# PA_Channel.net
KiCad netlist of a schematic drawn in Altium Designer
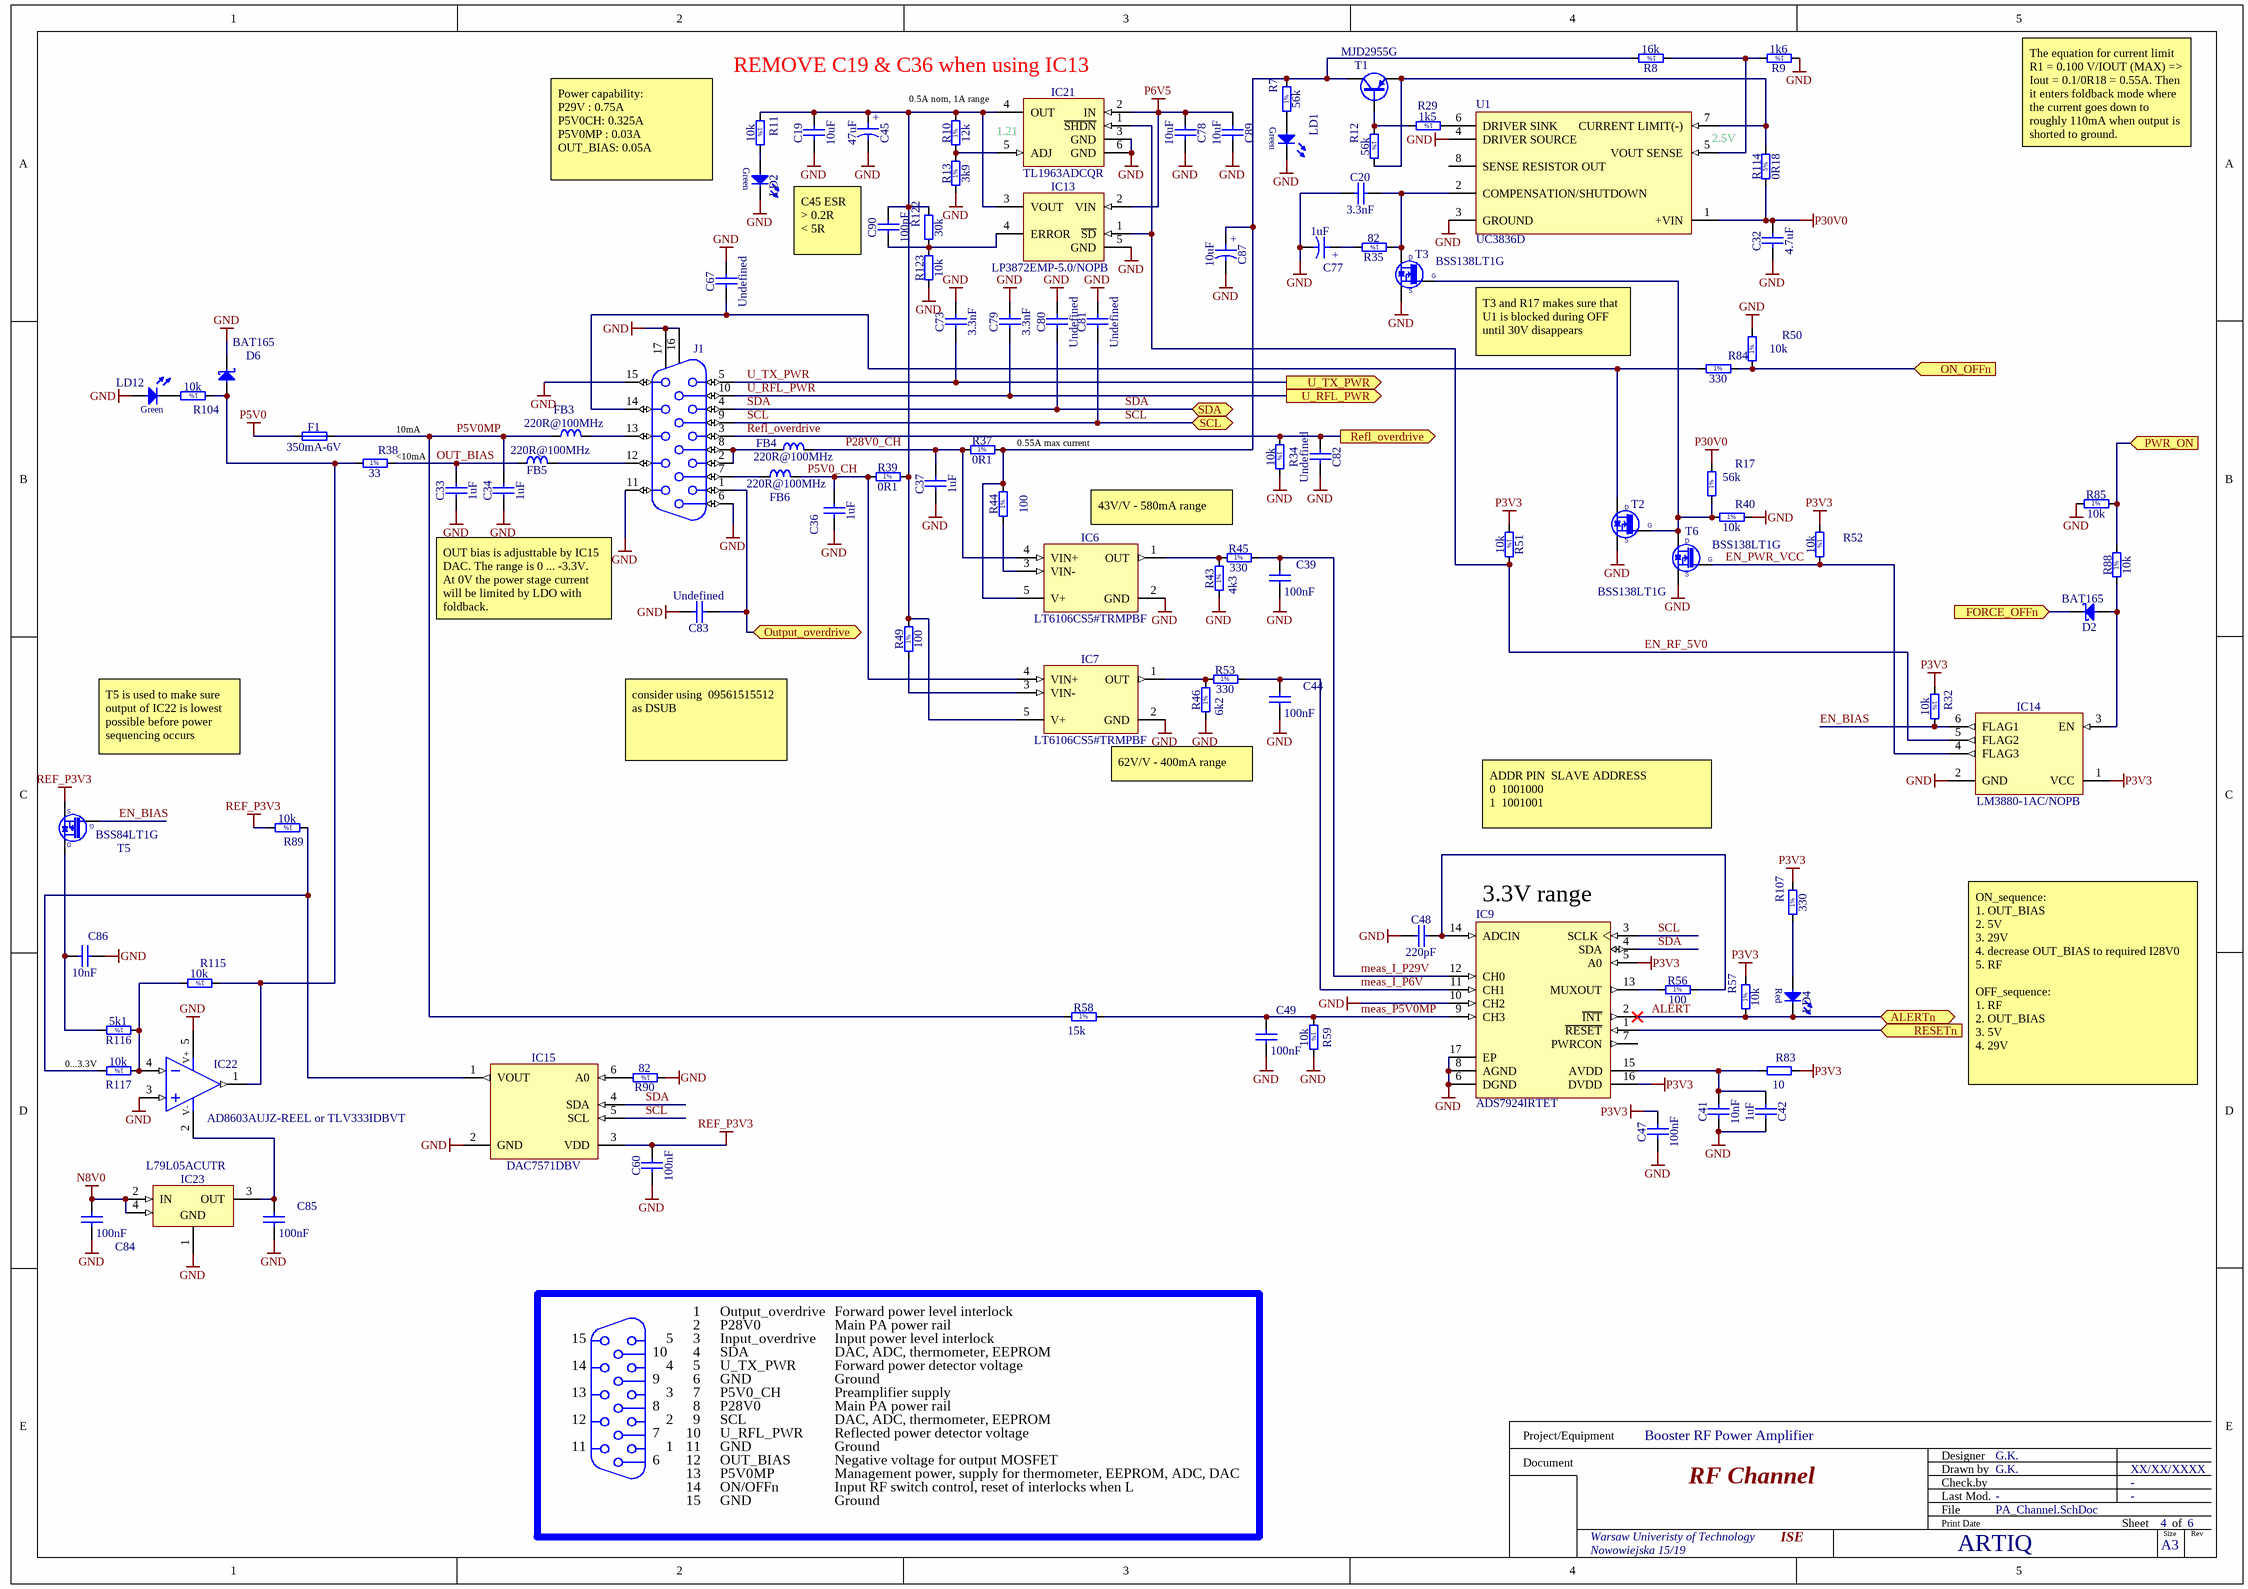
[diagram p0: PA_Channel.SchDoc]

(export (version "E")
  (design (tool "Eeschema 10.0.6"))
  (components
    (comp (ref "C19")
      (value "10uF")
      (footprint "CAPC2012X135N")
      (description "Non-polarised capacitor")
      (fields (field (name "PART NUMBER") "CC0805_10UF_16V_10%_X5R") (field (name "VOLTAGE") "16V"))
      (libsource (lib "Capacitors") (part "Capacitor - non polarized"))
    )
    (comp (ref "C20")
      (value "3.3nF")
      (footprint "CAPC1005X55N")
      (description "Non-polarised capacitor")
      (fields (field (name "PART NUMBER") "CC0402_3.3NF_50V_10%_X7R") (field (name "VOLTAGE") "50V"))
      (libsource (lib "Capacitors") (part "Capacitor - non polarized"))
    )
    (comp (ref "C32")
      (value "4.7uF")
      (footprint "CAPC3216X180N")
      (description "Non-polarised capacitor")
      (fields (field (name "PART NUMBER") "CC1206_4.7UF_50V_+80%-20%_Y5V") (field (name "VOLTAGE") "50V"))
      (libsource (lib "Capacitors") (part "Capacitor - non polarized"))
    )
    (comp (ref "C33")
      (value "1uF")
      (footprint "CAPC2012X110N")
      (description "Non-polarised capacitor")
      (fields (field (name "PART NUMBER") "CC0805_1UF_50V_10%_X7R") (field (name "VOLTAGE") "50V"))
      (libsource (lib "Capacitors") (part "Capacitor - non polarized"))
    )
    (comp (ref "C34")
      (value "1uF")
      (footprint "CAPC2012X110N")
      (description "Non-polarised capacitor")
      (fields (field (name "PART NUMBER") "CC0805_1UF_50V_10%_X7R") (field (name "VOLTAGE") "50V"))
      (libsource (lib "Capacitors") (part "Capacitor - non polarized"))
    )
    (comp (ref "C36")
      (value "1uF")
      (footprint "CAPC2012X110N")
      (description "Non-polarised capacitor")
      (fields (field (name "PART NUMBER") "CC0805_1UF_50V_10%_X7R") (field (name "VOLTAGE") "50V"))
      (libsource (lib "Capacitors") (part "Capacitor - non polarized"))
    )
    (comp (ref "C37")
      (value "1uF")
      (footprint "CAPC2012X110N")
      (description "Non-polarised capacitor")
      (fields (field (name "PART NUMBER") "CC0805_1UF_50V_10%_X7R") (field (name "VOLTAGE") "50V"))
      (libsource (lib "Capacitors") (part "Capacitor - non polarized"))
    )
    (comp (ref "C39")
      (value "100nF")
      (footprint "CAPC1005X55N")
      (description "Non-polarised capacitor")
      (fields (field (name "PART NUMBER") "CC0402_100NF_16V_10%_X7R") (field (name "VOLTAGE") "16V"))
      (libsource (lib "Capacitors") (part "Capacitor - non polarized"))
    )
    (comp (ref "C41")
      (value "10nF")
      (footprint "CAPC1005X55N")
      (description "Non-polarised capacitor")
      (fields (field (name "PART NUMBER") "CC0402_10NF_16V_10%_X7R") (field (name "VOLTAGE") "16V"))
      (libsource (lib "Capacitors") (part "Capacitor - non polarized"))
    )
    (comp (ref "C42")
      (value "1uF")
      (footprint "CAPC1005X55N")
      (description "Non-polarised capacitor")
      (fields (field (name "PART NUMBER") "CC0402_1UF_16V_10%_X5R") (field (name "VOLTAGE") "16V"))
      (libsource (lib "Capacitors") (part "Capacitor - non polarized"))
    )
    (comp (ref "C44")
      (value "100nF")
      (footprint "CAPC1005X55N")
      (description "Non-polarised capacitor")
      (fields (field (name "PART NUMBER") "CC0402_100NF_16V_10%_X7R") (field (name "VOLTAGE") "16V"))
      (libsource (lib "Capacitors") (part "Capacitor - non polarized"))
    )
    (comp (ref "C45")
      (value "47uF")
      (footprint "CAPMP3528X210N")
      (description "Polarised capacitor")
      (fields
        (field (name "PART NUMBER") "CTE3528-21_47UF_6.3V_10%_LESR0250")
        (field (name "VOLTAGE") "6.3V")
      )
      (libsource (lib "Capacitors") (part "Capacitor - polarized"))
    )
    (comp (ref "C47")
      (value "100nF")
      (footprint "CAPC1005X55N")
      (description "Non-polarised capacitor")
      (fields (field (name "PART NUMBER") "CC0402_100NF_16V_10%_X7R") (field (name "VOLTAGE") "16V"))
      (libsource (lib "Capacitors") (part "Capacitor - non polarized"))
    )
    (comp (ref "C48")
      (value "220pF")
      (footprint "CAPC1005X55N")
      (description "Non-polarised capacitor")
      (fields (field (name "PART NUMBER") "CC0402_220PF_50V_5%_C0G") (field (name "MANUFACTURER") "GENERIC"))
      (libsource (lib "Capacitors") (part "Capacitor - non polarized"))
    )
    (comp (ref "C49")
      (value "100nF")
      (footprint "CAPC1005X55N")
      (description "Non-polarised capacitor")
      (fields (field (name "PART NUMBER") "CC0402_100NF_16V_10%_X7R") (field (name "VOLTAGE") "16V"))
      (libsource (lib "Capacitors") (part "Capacitor - non polarized"))
    )
    (comp (ref "C60")
      (value "100nF")
      (footprint "CAPC1005X55N")
      (description "Non-polarised capacitor")
      (fields (field (name "PART NUMBER") "CC0402_100NF_16V_10%_X7R") (field (name "VOLTAGE") "16V"))
      (libsource (lib "Capacitors") (part "Capacitor - non polarized"))
    )
    (comp (ref "C67")
      (value "Undefined")
      (footprint "CAPC1005X55N")
      (description "Non-polarised capacitor")
      (fields (field (name "PART NUMBER") "CC0402_NO-VALUE"))
      (libsource (lib "Capacitors") (part "Capacitor - non polarized"))
    )
    (comp (ref "C73")
      (value "3.3nF")
      (footprint "CAPC1005X55N")
      (description "Non-polarised capacitor")
      (fields (field (name "PART NUMBER") "CC0402_3.3NF_50V_10%_X7R") (field (name "MANUFACTURER") "GENERIC"))
      (libsource (lib "Capacitors") (part "Capacitor - non polarized"))
    )
    (comp (ref "C77")
      (value "1uF")
      (footprint "CAPMP3216X180N")
      (description "Polarised capacitor")
      (fields (field (name "PART NUMBER") "CTE3216-18_1UF_16V_10%") (field (name "VOLTAGE") "16V"))
      (libsource (lib "Capacitors") (part "Capacitor - polarized"))
    )
    (comp (ref "C78")
      (value "10uF")
      (footprint "CAPC2012X135N")
      (description "Non-polarised capacitor")
      (fields (field (name "PART NUMBER") "CC0805_10UF_16V_10%_X5R") (field (name "VOLTAGE") "16V"))
      (libsource (lib "Capacitors") (part "Capacitor - non polarized"))
    )
    (comp (ref "C79")
      (value "3.3nF")
      (footprint "CAPC1005X55N")
      (description "Non-polarised capacitor")
      (fields (field (name "PART NUMBER") "CC0402_3.3NF_50V_10%_X7R") (field (name "MANUFACTURER") "GENERIC"))
      (libsource (lib "Capacitors") (part "Capacitor - non polarized"))
    )
    (comp (ref "C80")
      (value "Undefined")
      (footprint "CAPC1005X55N")
      (description "Non-polarised capacitor")
      (fields (field (name "PART NUMBER") "CC0402_NO-VALUE"))
      (libsource (lib "Capacitors") (part "Capacitor - non polarized"))
    )
    (comp (ref "C81")
      (value "Undefined")
      (footprint "CAPC1005X55N")
      (description "Non-polarised capacitor")
      (fields (field (name "PART NUMBER") "CC0402_NO-VALUE"))
      (libsource (lib "Capacitors") (part "Capacitor - non polarized"))
    )
    (comp (ref "C82")
      (value "Undefined")
      (footprint "CAPC1005X55N")
      (description "Non-polarised capacitor")
      (fields (field (name "PART NUMBER") "CC0402_NO-VALUE"))
      (libsource (lib "Capacitors") (part "Capacitor - non polarized"))
    )
    (comp (ref "C83")
      (value "Undefined")
      (footprint "CAPC1005X55N")
      (description "Non-polarised capacitor")
      (fields (field (name "PART NUMBER") "CC0402_NO-VALUE"))
      (libsource (lib "Capacitors") (part "Capacitor - non polarized"))
    )
    (comp (ref "C84")
      (value "100nF")
      (footprint "CAPC1005X55N")
      (description "Non-polarised capacitor")
      (fields (field (name "PART NUMBER") "CC0402_100NF_16V_10%_X7R") (field (name "VOLTAGE") "16V"))
      (libsource (lib "Capacitors") (part "Capacitor - non polarized"))
    )
    (comp (ref "C85")
      (value "100nF")
      (footprint "CAPC1005X55N")
      (description "Non-polarised capacitor")
      (fields (field (name "PART NUMBER") "CC0402_100NF_16V_10%_X7R") (field (name "VOLTAGE") "16V"))
      (libsource (lib "Capacitors") (part "Capacitor - non polarized"))
    )
    (comp (ref "C86")
      (value "10nF")
      (footprint "CAPC1608X87N")
      (description "Non-polarised capacitor")
      (fields (field (name "PART NUMBER") "CC0603_10NF_50V_5%_C0G") (field (name "VOLTAGE") "50V"))
      (libsource (lib "Capacitors") (part "Capacitor - non polarized"))
    )
    (comp (ref "C87")
      (value "10uF")
      (footprint "CAPMP6032X280N")
      (description "Polarised capacitor")
      (fields (field (name "PART NUMBER") "CTE6032-28_10UF_35V_10%") (field (name "VOLTAGE") "35V"))
      (libsource (lib "Capacitors") (part "Capacitor - polarized"))
    )
    (comp (ref "C89")
      (value "10uF")
      (footprint "CAPC2012X135N")
      (description "Non-polarised capacitor")
      (fields (field (name "PART NUMBER") "CC0805_10UF_16V_10%_X5R") (field (name "VOLTAGE") "16V"))
      (libsource (lib "Capacitors") (part "Capacitor - non polarized"))
    )
    (comp (ref "C90")
      (value "100pF")
      (footprint "CAPC1005X55N")
      (description "Non-polarised capacitor")
      (fields (field (name "PART NUMBER") "CC0402_100PF_50V_5%_C0G") (field (name "VOLTAGE") "50V"))
      (libsource (lib "Capacitors") (part "Capacitor - non polarized"))
    )
    (comp (ref "D2")
      (value "BAT165")
      (footprint "SOD2512X110N")
      (description "Schottky Diode")
      (fields (field (name "VOLTAGE") "40V") (field (name "POWER") "750mA"))
      (libsource (lib "ICs And Semiconductors") (part "Diode Schottky"))
    )
    (comp (ref "D6")
      (value "BAT165")
      (footprint "SOD2512X110N")
      (description "Schottky Diode")
      (fields (field (name "VOLTAGE") "40V") (field (name "POWER") "750mA"))
      (libsource (lib "ICs And Semiconductors") (part "Diode Schottky"))
    )
    (comp (ref "F1")
      (value "350mA-6V")
      (footprint "FUSR_TYCO_MICROSMD035F")
      (description "Fuse")
      (fields
        (field (name "PART NUMBER") "FUSR1210_TYCO_MICROSMD035F-2")
        (field (name "MANUFACTURER") "TYCO ELECTRONICS")
      )
      (libsource (lib "Eletro-mechanical") (part "Fuse"))
    )
    (comp (ref "FB3")
      (value "220R@100MHz")
      (footprint "INDC2012X105N")
      (description "Inductor")
      (fields (field (name "PART NUMBER") "IND0805_MURATA_BLM21PG221SN1D") (field (name "POWER") "2A"))
      (libsource (lib "Inductors & Transformers") (part "Inductor"))
    )
    (comp (ref "FB4")
      (value "220R@100MHz")
      (footprint "INDC2012X105N")
      (description "Inductor")
      (fields (field (name "PART NUMBER") "IND0805_MURATA_BLM21PG221SN1D") (field (name "POWER") "2A"))
      (libsource (lib "Inductors & Transformers") (part "Inductor"))
    )
    (comp (ref "FB5")
      (value "220R@100MHz")
      (footprint "INDC2012X105N")
      (description "Inductor")
      (fields (field (name "PART NUMBER") "IND0805_MURATA_BLM21PG221SN1D") (field (name "POWER") "2A"))
      (libsource (lib "Inductors & Transformers") (part "Inductor"))
    )
    (comp (ref "FB6")
      (value "220R@100MHz")
      (footprint "INDC2012X105N")
      (description "Inductor")
      (fields (field (name "PART NUMBER") "IND0805_MURATA_BLM21PG221SN1D") (field (name "POWER") "2A"))
      (libsource (lib "Inductors & Transformers") (part "Inductor"))
    )
    (comp (ref "IC6")
      (value "LT6106CS5#TRMPBF")
      (footprint "SOT95P280X145-5N")
      (description "Current Shunt Monitor -16V to +80V Common-Mode Range")
      (fields (field (name "MANUFACTURER") "ANALOG DEVICES"))
      (libsource (lib "ICs_Analog_Interfaces") (part "AMP_LT6106"))
    )
    (comp (ref "IC7")
      (value "LT6106CS5#TRMPBF")
      (footprint "SOT95P280X145-5N")
      (description "Current Shunt Monitor -16V to +80V Common-Mode Range")
      (fields (field (name "MANUFACTURER") "ANALOG DEVICES"))
      (libsource (lib "ICs_Analog_Interfaces") (part "AMP_LT6106"))
    )
    (comp (ref "IC9")
      (value "ADS7924IRTET")
      (footprint "TI-RTE16-1700X1700TP_V")
      (fields (field (name "MANUFACTURER") "Texas Instruments"))
      (libsource (lib "Altium Content Vault") (part "CMP-0003-02162-1"))
    )
    (comp (ref "IC13")
      (value "LP3872EMP-5.0/NOPB")
      (footprint "SOT150P700X180-5N")
      (description "1.5-A, low-dropout voltage regulator with  enable")
      (fields (field (name "MANUFACTURER") "TEXAS INSTRUMENTS"))
      (libsource (lib "Regulators_SMPS") (part "REG_LP3872EMP-5.0/NOPB"))
    )
    (comp (ref "IC14")
      (value "LM3880-1AC/NOPB")
      (footprint "SOT95P280X145-6N")
      (description "Simple Power Sequencer")
      (fields (field (name "MANUFACTURER") "TEXAS INSTRUMENTS"))
      (libsource (lib "ICs And Semiconductors") (part "LM3880"))
    )
    (comp (ref "IC15")
      (value "DAC7571DBV")
      (footprint "SOT95P280X145-6N")
      (description "+2.7 V to +5.5 V, I2C Interface (Receive Only), Voltage Output, 12-Bit Digital-To-Analog Converter")
      (fields (field (name "MANUFACTURER") "TEXAS INSTRUMENTS"))
      (libsource (lib "ICs And Semiconductors") (part "DAC7571"))
    )
    (comp (ref "IC21")
      (value "TL1963ADCQR")
      (footprint "SOT127P700X180-6N")
      (description "1.2V to 20V, 1.5A, Fast Transient Response, Low Noise, LDO Adjustable Regulator")
      (fields (field (name "MANUFACTURER") "TEXAS INSTRUMENTS"))
      (libsource (lib "ICs And Semiconductors") (part "TL1963ADCQR"))
    )
    (comp (ref "IC22")
      (value "AD8603AUJZ-REEL or TLV333IDBVT")
      (footprint "SOT95P280X100-5N")
      (description "Precision Micropower, Low Noise CMOS, Rail-to-Rail Input/Output Operational Amplifier")
      (fields
        (field (name "MANUFACTURER") "ANALOG DEVICES / Texas")
        (field (name "MANUFACTURER PART NUMBER") "AD8603AUJZ-REEL  or TLV333IDBVT")
      )
      (libsource (lib "ICs And Semiconductors") (part "AD8603AUJZ"))
    )
    (comp (ref "IC23")
      (value "L79L05ACUTR")
      (footprint "SOT89_4")
      (description "3-Terminal Regulator 1=GND 2=IN 3=OUT 4=IN")
      (fields (field (name "MANUFACTURER") "ST MICROELECTRONICS"))
      (libsource (lib "LIBRARY_SCH") (part "REG_7905_SOT89"))
    )
    (comp (ref "J1")
      (value "HD-Sub")
      (footprint "TYCO_1932144-1")
      (description "Connector High Density D-sub 15 Female")
      (fields (field (name "PART NUMBER") "9561515512") (field (name "MANUFACTURER") "HARTING"))
      (libsource (lib "LIBRARY_SCH") (part "HARTING 9561515512"))
    )
    (comp (ref "LD1")
      (value "Green")
      (footprint "LED_KINGBRIGHT_KPH-1608CGCK")
      (description "LED Green 1C 2A")
      (fields
        (field (name "PART NUMBER") "LED_KINGBRIGHT_KPH-1608CGCK")
        (field (name "MANUFACTURER") "KINGBRIGHT")
      )
      (libsource (lib "ICs And Semiconductors") (part "LED Green 1C 2A"))
    )
    (comp (ref "LD2")
      (value "Green")
      (footprint "LED_KINGBRIGHT_KPH-1608CGCK")
      (description "LED Green 1C 2A")
      (fields
        (field (name "PART NUMBER") "LED_KINGBRIGHT_KPH-1608CGCK")
        (field (name "MANUFACTURER") "KINGBRIGHT")
      )
      (libsource (lib "ICs And Semiconductors") (part "LED Green 1C 2A"))
    )
    (comp (ref "LD4")
      (value "Hyper Red")
      (footprint "LED_KINGBRIGHT_KPH-1608SURCK")
      (description "LED Red 1C 2A")
      (fields
        (field (name "PART NUMBER") "LED_KINGBRIGHT_KPH-1608SURCK")
        (field (name "MANUFACTURER") "KINGBRIGHT")
      )
      (libsource (lib "ICs And Semiconductors") (part "LED Red 1C 2A"))
    )
    (comp (ref "LD12")
      (value "Green")
      (footprint "LED_KINGBRIGHT_KPH-1608CGCK")
      (description "LED Green 1C 2A")
      (fields
        (field (name "PART NUMBER") "LED_KINGBRIGHT_KPH-1608CGCK")
        (field (name "MANUFACTURER") "KINGBRIGHT")
      )
      (libsource (lib "ICs And Semiconductors") (part "LED Green 1C 2A"))
    )
    (comp (ref "R7")
      (value "56k")
      (footprint "RESC1608X55N")
      (description "Resistor - 1%")
      (fields (field (name "PART NUMBER") "R0603_56K_1%_0.1W_100PPM") (field (name "POWER") "0.1W"))
      (libsource (lib "Resistors") (part "Resistor - 1%"))
    )
    (comp (ref "R8")
      (value "16k")
      (footprint "RESC1608X55N")
      (description "Resistor - 1%")
      (fields (field (name "PART NUMBER") "R0603_16K_1%_0.1W_100PPM") (field (name "POWER") "0.1W"))
      (libsource (lib "Resistors") (part "Resistor - 1%"))
    )
    (comp (ref "R9")
      (value "1k6")
      (footprint "RESC1608X55N")
      (description "Resistor - 1%")
      (fields (field (name "PART NUMBER") "R0603_1K6_1%_0.1W_100PPM") (field (name "POWER") "0.1W"))
      (libsource (lib "Resistors") (part "Resistor - 1%"))
    )
    (comp (ref "R10")
      (value "12k")
      (footprint "RESC1005X40N")
      (description "Resistor - 1%")
      (fields (field (name "PART NUMBER") "R0402_12K_1%_0.0625W_100PPM") (field (name "POWER") "0.0625W"))
      (libsource (lib "") (part "Resistor - 1%_1"))
    )
    (comp (ref "R11")
      (value "10k")
      (footprint "RESC1005X40N")
      (description "Resistor - 1%")
      (fields (field (name "PART NUMBER") "R0402_10K_1%_0.0625W_100PPM") (field (name "POWER") "0.0625W"))
      (libsource (lib "") (part "Resistor - 1%_1"))
    )
    (comp (ref "R12")
      (value "56k")
      (footprint "RESC1608X55N")
      (description "Resistor - 1%")
      (fields (field (name "PART NUMBER") "R0603_56K_1%_0.1W_100PPM") (field (name "POWER") "0.1W"))
      (libsource (lib "Resistors") (part "Resistor - 1%"))
    )
    (comp (ref "R13")
      (value "3k9")
      (footprint "RESC1005X40N")
      (description "Resistor - 1%")
      (fields (field (name "PART NUMBER") "R0402_3K9_1%_0.0625W_100PPM") (field (name "POWER") "0.0625W"))
      (libsource (lib "") (part "Resistor - 1%_1"))
    )
    (comp (ref "R17")
      (value "56k")
      (footprint "RESC1608X55N")
      (description "Resistor - 1%")
      (fields (field (name "PART NUMBER") "R0603_56K_1%_0.1W_100PPM") (field (name "POWER") "0.1W"))
      (libsource (lib "Resistors") (part "Resistor - 1%"))
    )
    (comp (ref "R29")
      (value "1k5")
      (footprint "RESC1608X55N")
      (description "Resistor - 1%")
      (fields (field (name "PART NUMBER") "R0603_1K5_1%_0.1W_100PPM") (field (name "POWER") "0.1W"))
      (libsource (lib "Resistors") (part "Resistor - 1%"))
    )
    (comp (ref "R32")
      (value "10k")
      (footprint "RESC1005X40N")
      (description "Resistor - 1%")
      (fields (field (name "PART NUMBER") "R0402_10K_1%_0.0625W_100PPM") (field (name "POWER") "0.0625W"))
      (libsource (lib "") (part "Resistor - 1%_1"))
    )
    (comp (ref "R34")
      (value "10k")
      (footprint "RESC1005X40N")
      (description "Resistor - 1%")
      (fields (field (name "PART NUMBER") "R0402_10K_1%_0.0625W_100PPM") (field (name "POWER") "0.0625W"))
      (libsource (lib "") (part "Resistor - 1%_1"))
    )
    (comp (ref "R35")
      (value "82")
      (footprint "RESC1005X40N")
      (description "Resistor - 1%")
      (fields (field (name "PART NUMBER") "R0402_82R_1%_0.0625W_100PPM") (field (name "POWER") "0.0625W"))
      (libsource (lib "") (part "Resistor - 1%_1"))
    )
    (comp (ref "R37")
      (value "0R1")
      (footprint "RESC3216X65N")
      (description "Resistor - 1%")
      (fields
        (field (name "PART NUMBER") "R1206_0R1_1%_0.25W_100PPM_YAGEO_PT")
        (field (name "POWER") "0.25W")
      )
      (libsource (lib "Resistors") (part "Resistor - 1%"))
    )
    (comp (ref "R38")
      (value "33")
      (footprint "RESC3216X65N")
      (description "Resistor - 1%")
      (fields (field (name "PART NUMBER") "R1206_33R_1%_0.25W_100PPM") (field (name "POWER") "0.25W"))
      (libsource (lib "Resistors") (part "Resistor - 1%"))
    )
    (comp (ref "R39")
      (value "0R1")
      (footprint "RESC3216X65N")
      (description "Resistor - 1%")
      (fields
        (field (name "PART NUMBER") "R1206_0R1_1%_0.25W_100PPM_YAGEO_PT")
        (field (name "POWER") "0.25W")
      )
      (libsource (lib "Resistors") (part "Resistor - 1%"))
    )
    (comp (ref "R40")
      (value "10k")
      (footprint "RESC1005X40N")
      (description "Resistor - 1%")
      (fields (field (name "PART NUMBER") "R0402_10K_1%_0.0625W_100PPM") (field (name "POWER") "0.0625W"))
      (libsource (lib "") (part "Resistor - 1%_1"))
    )
    (comp (ref "R43")
      (value "4k3")
      (footprint "RESC1608X55N")
      (description "Resistor - 1%")
      (fields (field (name "PART NUMBER") "R0603_4K3_1%_0.1W_100PPM") (field (name "POWER") "0.1W"))
      (libsource (lib "Resistors") (part "Resistor - 1%"))
    )
    (comp (ref "R44")
      (value "100")
      (footprint "RESC1005X40N")
      (description "Resistor - 1%")
      (fields (field (name "PART NUMBER") "R0402_100R_1%_0.0625W_100PPM") (field (name "POWER") "0.0625W"))
      (libsource (lib "") (part "Resistor - 1%_1"))
    )
    (comp (ref "R45")
      (value "330")
      (footprint "RESC1608X55N")
      (description "Resistor - 1%")
      (fields (field (name "PART NUMBER") "R0603_330R_1%_0.1W_100PPM") (field (name "POWER") "0.1W"))
      (libsource (lib "Resistors") (part "Resistor - 1%"))
    )
    (comp (ref "R46")
      (value "6k2")
      (footprint "RESC1608X55N")
      (description "Resistor - 1%")
      (fields (field (name "PART NUMBER") "R0603_6K2_1%_0.1W_100PPM") (field (name "POWER") "0.1W"))
      (libsource (lib "Resistors") (part "Resistor - 1%"))
    )
    (comp (ref "R49")
      (value "100")
      (footprint "RESC1005X40N")
      (description "Resistor - 1%")
      (fields (field (name "PART NUMBER") "R0402_100R_1%_0.0625W_100PPM") (field (name "POWER") "0.0625W"))
      (libsource (lib "") (part "Resistor - 1%_1"))
    )
    (comp (ref "R50")
      (value "10k")
      (footprint "RESC1005X40N")
      (description "Resistor - 1%")
      (fields (field (name "PART NUMBER") "R0402_10K_1%_0.0625W_100PPM") (field (name "POWER") "0.0625W"))
      (libsource (lib "") (part "Resistor - 1%_1"))
    )
    (comp (ref "R51")
      (value "10k")
      (footprint "RESC1005X40N")
      (description "Resistor - 1%")
      (fields (field (name "PART NUMBER") "R0402_10K_1%_0.0625W_100PPM") (field (name "POWER") "0.0625W"))
      (libsource (lib "") (part "Resistor - 1%_1"))
    )
    (comp (ref "R52")
      (value "10k")
      (footprint "RESC1005X40N")
      (description "Resistor - 1%")
      (fields (field (name "PART NUMBER") "R0402_10K_1%_0.0625W_100PPM") (field (name "POWER") "0.0625W"))
      (libsource (lib "") (part "Resistor - 1%_1"))
    )
    (comp (ref "R53")
      (value "330")
      (footprint "RESC1608X55N")
      (description "Resistor - 1%")
      (fields (field (name "PART NUMBER") "R0603_330R_1%_0.1W_100PPM") (field (name "POWER") "0.1W"))
      (libsource (lib "Resistors") (part "Resistor - 1%"))
    )
    (comp (ref "R56")
      (value "100")
      (footprint "RESC1608X55N")
      (description "Resistor - 1%")
      (fields (field (name "PART NUMBER") "R0603_100R_1%_0.1W_100PPM") (field (name "POWER") "0.1W"))
      (libsource (lib "Resistors") (part "Resistor - 1%"))
    )
    (comp (ref "R57")
      (value "10k")
      (footprint "RESC1005X40N")
      (description "Resistor - 1%")
      (fields (field (name "PART NUMBER") "R0402_10K_1%_0.0625W_100PPM") (field (name "POWER") "0.0625W"))
      (libsource (lib "") (part "Resistor - 1%_1"))
    )
    (comp (ref "R58")
      (value "15k")
      (footprint "RESC1005X40N")
      (description "Resistor - 1%")
      (fields (field (name "PART NUMBER") "R0402_15K_1%_0.0625W_100PPM") (field (name "POWER") "0.0625W"))
      (libsource (lib "") (part "Resistor - 1%_1"))
    )
    (comp (ref "R59")
      (value "10k")
      (footprint "RESC1005X40N")
      (description "Resistor - 1%")
      (fields (field (name "PART NUMBER") "R0402_10K_1%_0.0625W_100PPM") (field (name "POWER") "0.0625W"))
      (libsource (lib "") (part "Resistor - 1%_1"))
    )
    (comp (ref "R83")
      (value "10")
      (footprint "RESC1005X40N")
      (description "Resistor - 1%")
      (fields (field (name "PART NUMBER") "R0402_10R_1%_0.0625W_200PPM") (field (name "POWER") "0.0625W"))
      (libsource (lib "") (part "Resistor - 1%_1"))
    )
    (comp (ref "R84")
      (value "330")
      (footprint "RESC1608X55N")
      (description "Resistor - 1%")
      (fields (field (name "PART NUMBER") "R0603_330R_1%_0.1W_100PPM") (field (name "POWER") "0.1W"))
      (libsource (lib "Resistors") (part "Resistor - 1%"))
    )
    (comp (ref "R85")
      (value "10k")
      (footprint "RESC1005X40N")
      (description "Resistor - 1%")
      (fields (field (name "PART NUMBER") "R0402_10K_1%_0.0625W_100PPM") (field (name "POWER") "0.0625W"))
      (libsource (lib "") (part "Resistor - 1%_1"))
    )
    (comp (ref "R88")
      (value "10k")
      (footprint "RESC1005X40N")
      (description "Resistor - 1%")
      (fields (field (name "PART NUMBER") "R0402_10K_1%_0.0625W_100PPM") (field (name "POWER") "0.0625W"))
      (libsource (lib "") (part "Resistor - 1%_1"))
    )
    (comp (ref "R89")
      (value "10k")
      (footprint "RESC1005X40N")
      (description "Resistor - 1%")
      (fields (field (name "PART NUMBER") "R0402_10K_1%_0.0625W_100PPM") (field (name "POWER") "0.0625W"))
      (libsource (lib "") (part "Resistor - 1%_1"))
    )
    (comp (ref "R90")
      (value "82")
      (footprint "RESC1005X40N")
      (description "Resistor - 1%")
      (fields (field (name "PART NUMBER") "R0402_82R_1%_0.0625W_100PPM") (field (name "POWER") "0.0625W"))
      (libsource (lib "") (part "Resistor - 1%_1"))
    )
    (comp (ref "R104")
      (value "10k")
      (footprint "RESC1005X40N")
      (description "Resistor - 1%")
      (fields (field (name "PART NUMBER") "R0402_10K_1%_0.0625W_100PPM") (field (name "POWER") "0.0625W"))
      (libsource (lib "") (part "Resistor - 1%_1"))
    )
    (comp (ref "R107")
      (value "330")
      (footprint "RESC1608X55N")
      (description "Resistor - 1%")
      (fields (field (name "PART NUMBER") "R0603_330R_1%_0.1W_100PPM") (field (name "POWER") "0.1W"))
      (libsource (lib "Resistors") (part "Resistor - 1%"))
    )
    (comp (ref "R114")
      (value "0R18")
      (footprint "RESC2012X70N")
      (description "Resistor - 5%")
      (fields
        (field (name "PART NUMBER") "R0805_0R18_5%_0.25W_250PPM_PANASONIC_ERJ")
        (field (name "POWER") "0.25W")
      )
      (libsource (lib "Resistors") (part "Resistor - 5%"))
    )
    (comp (ref "R115")
      (value "10k")
      (footprint "RESC1005X40N")
      (description "Resistor - 1%")
      (fields (field (name "PART NUMBER") "R0402_10K_1%_0.0625W_100PPM") (field (name "POWER") "0.0625W"))
      (libsource (lib "") (part "Resistor - 1%_1"))
    )
    (comp (ref "R116")
      (value "5k1")
      (footprint "RESC1005X40N")
      (description "Resistor - 1%")
      (fields (field (name "PART NUMBER") "R0402_5K1_1%_0.0625W_100PPM") (field (name "POWER") "0.0625W"))
      (libsource (lib "") (part "Resistor - 1%_1"))
    )
    (comp (ref "R117")
      (value "10k")
      (footprint "RESC1005X40N")
      (description "Resistor - 1%")
      (fields (field (name "PART NUMBER") "R0402_10K_1%_0.0625W_100PPM") (field (name "POWER") "0.0625W"))
      (libsource (lib "") (part "Resistor - 1%_1"))
    )
    (comp (ref "R122")
      (value "30k")
      (footprint "RESC1005X40N")
      (description "Resistor - 1%")
      (fields (field (name "PART NUMBER") "R0402_30K_1%_0.0625W_100PPM") (field (name "POWER") "0.0625W"))
      (libsource (lib "") (part "Resistor - 1%_1"))
    )
    (comp (ref "R123")
      (value "10k")
      (footprint "RESC1005X40N")
      (description "Resistor - 1%")
      (fields (field (name "PART NUMBER") "R0402_10K_1%_0.0625W_100PPM") (field (name "POWER") "0.0625W"))
      (libsource (lib "") (part "Resistor - 1%_1"))
    )
    (comp (ref "T1")
      (value "MJD2955G")
      (footprint "TO228P991X239-3N-R552X520")
      (description "PNP Transistor")
      (fields (field (name "MANUFACTURER") "ON SEMICONDUCTOR"))
      (libsource (lib "ICs And Semiconductors") (part "PNP B1 E2 C3"))
    )
    (comp (ref "T2")
      (value "BSS138LT1G")
      (footprint "SOT95P240X110-3N")
      (description "N-CHANNEL MOSFET WITH DIODE")
      (fields (field (name "MANUFACTURER") "ON SEMICONDUCTOR"))
      (libsource (lib "ICs And Semiconductors") (part "N-MOSFET-D 1G 2S 3D"))
    )
    (comp (ref "T3")
      (value "BSS138LT1G")
      (footprint "SOT95P240X110-3N")
      (description "N-CHANNEL MOSFET WITH DIODE")
      (fields (field (name "MANUFACTURER") "ON SEMICONDUCTOR"))
      (libsource (lib "ICs And Semiconductors") (part "N-MOSFET-D 1G 2S 3D"))
    )
    (comp (ref "T5")
      (value "BSS84LT1G")
      (footprint "SOT95P240X110-3N")
      (description "P-CHANNEL MOSFET WITH DIODE")
      (fields (field (name "MANUFACTURER") "ON SEMICONDUCTOR"))
      (libsource (lib "ICs And Semiconductors") (part "P-MOSFET-D 1G 2S 3D"))
    )
    (comp (ref "T6")
      (value "BSS138LT1G")
      (footprint "SOT95P240X110-3N")
      (description "N-CHANNEL MOSFET WITH DIODE")
      (fields (field (name "MANUFACTURER") "ON SEMICONDUCTOR"))
      (libsource (lib "ICs And Semiconductors") (part "N-MOSFET-D 1G 2S 3D"))
    )
    (comp (ref "U1")
      (value "UC3836D")
      (footprint "D0008A_M")
      (fields (field (name "MANUFACTURER") "Texas Instruments"))
      (libsource (lib "Altium Content Vault") (part "CMP-0322-00047-2"))
    )
  )
  (nets
    (net (code "1") (name "/ALERT") (class "Default")
      (node (ref "IC9") (pin "2") (pinfunction "~{INT}_2") (pintype "output"))
      (node (ref "LD4") (pin "1") (pinfunction "C_1") (pintype "passive"))
      (node (ref "R57") (pin "1") (pinfunction "1_1") (pintype "passive"))
    )
    (net (code "2") (name "/EN_BIAS") (class "Default")
      (node (ref "IC14") (pin "6") (pinfunction "FLAG1_6") (pintype "output"))
      (node (ref "R32") (pin "2") (pinfunction "2_2") (pintype "passive"))
      (node (ref "T5") (pin "1") (pinfunction "G_1") (pintype "passive"))
    )
    (net (code "3") (name "/EN_PWR_VCC") (class "Default")
      (node (ref "IC14") (pin "4") (pinfunction "FLAG3_4") (pintype "output"))
      (node (ref "R52") (pin "2") (pinfunction "2_2") (pintype "passive"))
      (node (ref "T6") (pin "1") (pinfunction "G_1") (pintype "passive"))
    )
    (net (code "4") (name "/EN_RF_5V0") (class "Default")
      (node (ref "IC13") (pin "1") (pinfunction "~{SD}_1") (pintype "input"))
      (node (ref "IC14") (pin "5") (pinfunction "FLAG2_5") (pintype "output"))
      (node (ref "IC21") (pin "1") (pinfunction "~{SHDN}_1") (pintype "input"))
      (node (ref "R51") (pin "2") (pinfunction "2_2") (pintype "passive"))
    )
    (net (code "5") (name "/FORCE_OFFn") (class "Default")
      (node (ref "D2") (pin "1") (pinfunction "C_1") (pintype "passive"))
    )
    (net (code "6") (name "/ON_OFFn") (class "Default")
      (node (ref "R50") (pin "1") (pinfunction "1_1") (pintype "passive"))
      (node (ref "R84") (pin "2") (pinfunction "2_2") (pintype "passive"))
    )
    (net (code "7") (name "/OUT_BIAS") (class "Default")
      (node (ref "C33") (pin "2") (pinfunction "2_2") (pintype "passive"))
      (node (ref "FB5") (pin "1") (pinfunction "1_1") (pintype "passive"))
      (node (ref "R38") (pin "2") (pinfunction "2_2") (pintype "passive"))
    )
    (net (code "8") (name "/Output_overdrive") (class "Default")
      (node (ref "C83") (pin "1") (pinfunction "1_1") (pintype "passive"))
      (node (ref "J1") (pin "1") (pinfunction "1_1") (pintype "bidirectional"))
    )
    (net (code "9") (name "/P5V0MP") (class "Default")
      (node (ref "C34") (pin "2") (pinfunction "2_2") (pintype "passive"))
      (node (ref "F1") (pin "2") (pinfunction "2_2") (pintype "passive"))
      (node (ref "FB3") (pin "1") (pinfunction "1_1") (pintype "passive"))
      (node (ref "R58") (pin "1") (pinfunction "1_1") (pintype "passive"))
    )
    (net (code "10") (name "/P5V0_CH") (class "Default")
      (node (ref "C36") (pin "2") (pinfunction "2_2") (pintype "passive"))
      (node (ref "FB6") (pin "2") (pinfunction "2_2") (pintype "passive"))
      (node (ref "IC7") (pin "4") (pinfunction "VIN+_4") (pintype "input"))
      (node (ref "R39") (pin "1") (pinfunction "1_1") (pintype "passive"))
    )
    (net (code "11") (name "/P28V0_CH") (class "Default")
      (node (ref "C37") (pin "2") (pinfunction "2_2") (pintype "passive"))
      (node (ref "FB4") (pin "2") (pinfunction "2_2") (pintype "passive"))
      (node (ref "IC6") (pin "4") (pinfunction "VIN+_4") (pintype "input"))
      (node (ref "R37") (pin "1") (pinfunction "1_1") (pintype "passive"))
    )
    (net (code "12") (name "/PWR_ON") (class "Default")
      (node (ref "R85") (pin "2") (pinfunction "2_2") (pintype "passive"))
      (node (ref "R88") (pin "2") (pinfunction "2_2") (pintype "passive"))
    )
    (net (code "13") (name "/RESETn") (class "Default")
      (node (ref "IC9") (pin "1") (pinfunction "~{RESET}_1") (pintype "input"))
    )
    (net (code "14") (name "/Refl_overdrive") (class "Default")
      (node (ref "C82") (pin "1") (pinfunction "1_1") (pintype "passive"))
      (node (ref "J1") (pin "3") (pinfunction "3_3") (pintype "bidirectional"))
      (node (ref "R34") (pin "1") (pinfunction "1_1") (pintype "passive"))
    )
    (net (code "15") (name "/SCL") (class "Default")
      (node (ref "C81") (pin "1") (pinfunction "1_1") (pintype "passive"))
      (node (ref "IC15") (pin "5") (pinfunction "SCL_5") (pintype "input"))
      (node (ref "IC9") (pin "3") (pinfunction "SCLK_3") (pintype "input"))
      (node (ref "J1") (pin "9") (pinfunction "9_9") (pintype "bidirectional"))
    )
    (net (code "16") (name "/SDA") (class "Default")
      (node (ref "C80") (pin "1") (pinfunction "1_1") (pintype "passive"))
      (node (ref "IC15") (pin "4") (pinfunction "SDA_4") (pintype "input"))
      (node (ref "IC9") (pin "4") (pinfunction "SDA_4") (pintype "bidirectional"))
      (node (ref "J1") (pin "4") (pinfunction "4_4") (pintype "bidirectional"))
    )
    (net (code "17") (name "/U_RFL_PWR") (class "Default")
      (node (ref "C79") (pin "1") (pinfunction "1_1") (pintype "passive"))
      (node (ref "J1") (pin "10") (pinfunction "10_10") (pintype "bidirectional"))
    )
    (net (code "18") (name "/U_TX_PWR") (class "Default")
      (node (ref "C73") (pin "1") (pinfunction "1_1") (pintype "passive"))
      (node (ref "J1") (pin "5") (pinfunction "5_5") (pintype "bidirectional"))
    )
    (net (code "19") (name "/meas_I_P6V") (class "Default")
      (node (ref "C44") (pin "1") (pinfunction "1_1") (pintype "passive"))
      (node (ref "IC9") (pin "11") (pinfunction "CH1_11") (pintype "input"))
      (node (ref "R53") (pin "2") (pinfunction "2_2") (pintype "passive"))
    )
    (net (code "20") (name "/meas_I_P29V") (class "Default")
      (node (ref "C39") (pin "1") (pinfunction "1_1") (pintype "passive"))
      (node (ref "IC9") (pin "12") (pinfunction "CH0_12") (pintype "input"))
      (node (ref "R45") (pin "2") (pinfunction "2_2") (pintype "passive"))
    )
    (net (code "21") (name "/meas_P5V0MP") (class "Default")
      (node (ref "C49") (pin "1") (pinfunction "1_1") (pintype "passive"))
      (node (ref "IC9") (pin "9") (pinfunction "CH3_9") (pintype "input"))
      (node (ref "R58") (pin "2") (pinfunction "2_2") (pintype "passive"))
      (node (ref "R59") (pin "1") (pinfunction "1_1") (pintype "passive"))
    )
    (net (code "22") (name "GND") (class "Default")
      (node (ref "C19") (pin "1") (pinfunction "1_1") (pintype "passive"))
      (node (ref "C20") (pin "1") (pinfunction "1_1") (pintype "passive"))
      (node (ref "C32") (pin "1") (pinfunction "1_1") (pintype "passive"))
      (node (ref "C33") (pin "1") (pinfunction "1_1") (pintype "passive"))
      (node (ref "C34") (pin "1") (pinfunction "1_1") (pintype "passive"))
      (node (ref "C36") (pin "1") (pinfunction "1_1") (pintype "passive"))
      (node (ref "C37") (pin "1") (pinfunction "1_1") (pintype "passive"))
      (node (ref "C39") (pin "2") (pinfunction "2_2") (pintype "passive"))
      (node (ref "C41") (pin "1") (pinfunction "1_1") (pintype "passive"))
      (node (ref "C42") (pin "2") (pinfunction "2_2") (pintype "passive"))
      (node (ref "C44") (pin "2") (pinfunction "2_2") (pintype "passive"))
      (node (ref "C45") (pin "2") (pinfunction "2_2") (pintype "passive"))
      (node (ref "C47") (pin "1") (pinfunction "1_1") (pintype "passive"))
      (node (ref "C48") (pin "1") (pinfunction "1_1") (pintype "passive"))
      (node (ref "C49") (pin "2") (pinfunction "2_2") (pintype "passive"))
      (node (ref "C60") (pin "1") (pinfunction "1_1") (pintype "passive"))
      (node (ref "C67") (pin "2") (pinfunction "2_2") (pintype "passive"))
      (node (ref "C73") (pin "2") (pinfunction "2_2") (pintype "passive"))
      (node (ref "C77") (pin "2") (pinfunction "2_2") (pintype "passive"))
      (node (ref "C78") (pin "2") (pinfunction "2_2") (pintype "passive"))
      (node (ref "C79") (pin "2") (pinfunction "2_2") (pintype "passive"))
      (node (ref "C80") (pin "2") (pinfunction "2_2") (pintype "passive"))
      (node (ref "C81") (pin "2") (pinfunction "2_2") (pintype "passive"))
      (node (ref "C82") (pin "2") (pinfunction "2_2") (pintype "passive"))
      (node (ref "C83") (pin "2") (pinfunction "2_2") (pintype "passive"))
      (node (ref "C84") (pin "2") (pinfunction "2_2") (pintype "passive"))
      (node (ref "C85") (pin "2") (pinfunction "2_2") (pintype "passive"))
      (node (ref "C86") (pin "2") (pinfunction "2_2") (pintype "passive"))
      (node (ref "C87") (pin "2") (pinfunction "2_2") (pintype "passive"))
      (node (ref "C89") (pin "2") (pinfunction "2_2") (pintype "passive"))
      (node (ref "D6") (pin "1") (pinfunction "C_1") (pintype "passive"))
      (node (ref "IC13") (pin "5") (pinfunction "GND_5") (pintype "power_in"))
      (node (ref "IC14") (pin "2") (pinfunction "GND_2") (pintype "power_in"))
      (node (ref "IC15") (pin "2") (pinfunction "GND_2") (pintype "power_in"))
      (node (ref "IC21") (pin "3") (pinfunction "GND_3") (pintype "power_in"))
      (node (ref "IC21") (pin "6") (pinfunction "GND_6") (pintype "power_in"))
      (node (ref "IC22") (pin "3") (pinfunction "IN+_3") (pintype "input"))
      (node (ref "IC22") (pin "5") (pinfunction "V+_5") (pintype "power_in"))
      (node (ref "IC23") (pin "1") (pinfunction "GND_1") (pintype "power_in"))
      (node (ref "IC6") (pin "2") (pinfunction "GND_2") (pintype "power_in"))
      (node (ref "IC7") (pin "2") (pinfunction "GND_2") (pintype "power_in"))
      (node (ref "IC9") (pin "10") (pinfunction "CH2_10") (pintype "input"))
      (node (ref "IC9") (pin "17") (pinfunction "EP_17") (pintype "power_in"))
      (node (ref "IC9") (pin "6") (pinfunction "DGND_6") (pintype "power_in"))
      (node (ref "IC9") (pin "8") (pinfunction "AGND_8") (pintype "power_in"))
      (node (ref "J1") (pin "11") (pinfunction "11_11") (pintype "bidirectional"))
      (node (ref "J1") (pin "15") (pinfunction "15_15") (pintype "bidirectional"))
      (node (ref "J1") (pin "16") (pinfunction "16_16") (pintype "passive"))
      (node (ref "J1") (pin "17") (pinfunction "17_17") (pintype "passive"))
      (node (ref "J1") (pin "6") (pinfunction "6_6") (pintype "bidirectional"))
      (node (ref "LD1") (pin "1") (pinfunction "C_1") (pintype "passive"))
      (node (ref "LD12") (pin "2") (pinfunction "A_2") (pintype "passive"))
      (node (ref "LD2") (pin "1") (pinfunction "C_1") (pintype "passive"))
      (node (ref "R123") (pin "1") (pinfunction "1_1") (pintype "passive"))
      (node (ref "R13") (pin "1") (pinfunction "1_1") (pintype "passive"))
      (node (ref "R34") (pin "2") (pinfunction "2_2") (pintype "passive"))
      (node (ref "R40") (pin "2") (pinfunction "2_2") (pintype "passive"))
      (node (ref "R43") (pin "1") (pinfunction "1_1") (pintype "passive"))
      (node (ref "R46") (pin "1") (pinfunction "1_1") (pintype "passive"))
      (node (ref "R50") (pin "2") (pinfunction "2_2") (pintype "passive"))
      (node (ref "R59") (pin "2") (pinfunction "2_2") (pintype "passive"))
      (node (ref "R85") (pin "1") (pinfunction "1_1") (pintype "passive"))
      (node (ref "R9") (pin "1") (pinfunction "1_1") (pintype "passive"))
      (node (ref "R90") (pin "1") (pinfunction "1_1") (pintype "passive"))
      (node (ref "T2") (pin "2") (pinfunction "S_2") (pintype "passive"))
      (node (ref "T3") (pin "2") (pinfunction "S_2") (pintype "passive"))
      (node (ref "T6") (pin "2") (pinfunction "S_2") (pintype "passive"))
      (node (ref "U1") (pin "3") (pinfunction "GROUND_3") (pintype "power_in"))
      (node (ref "U1") (pin "4") (pinfunction "DRIVER_SOURCE_4") (pintype "passive"))
    )
    (net (code "23") (name "N8V0") (class "Default")
      (node (ref "C84") (pin "1") (pinfunction "1_1") (pintype "passive"))
      (node (ref "IC23") (pin "2") (pinfunction "IN_2") (pintype "input"))
      (node (ref "IC23") (pin "4") (pinfunction "IN_4") (pintype "input"))
    )
    (net (code "24") (name "Net-(C77-Pad1)") (class "Default")
      (node (ref "C77") (pin "1") (pinfunction "1_1") (pintype "passive"))
      (node (ref "R35") (pin "2") (pinfunction "2_2") (pintype "passive"))
    )
    (net (code "25") (name "Net-(D2-A)") (class "Default")
      (node (ref "D2") (pin "2") (pinfunction "A_2") (pintype "passive"))
      (node (ref "IC14") (pin "3") (pinfunction "EN_3") (pintype "input"))
      (node (ref "R88") (pin "1") (pinfunction "1_1") (pintype "passive"))
    )
    (net (code "26") (name "Net-(D6-A)") (class "Default")
      (node (ref "D6") (pin "2") (pinfunction "A_2") (pintype "passive"))
      (node (ref "IC22") (pin "1") (pinfunction "OUT_1") (pintype "output"))
      (node (ref "R104") (pin "1") (pinfunction "1_1") (pintype "passive"))
      (node (ref "R115") (pin "1") (pinfunction "1_1") (pintype "passive"))
      (node (ref "R38") (pin "1") (pinfunction "1_1") (pintype "passive"))
    )
    (net (code "27") (name "Net-(FB3-Pad2)") (class "Default")
      (node (ref "FB3") (pin "2") (pinfunction "2_2") (pintype "passive"))
      (node (ref "J1") (pin "13") (pinfunction "13_13") (pintype "bidirectional"))
    )
    (net (code "28") (name "Net-(FB4-Pad1)") (class "Default")
      (node (ref "FB4") (pin "1") (pinfunction "1_1") (pintype "passive"))
      (node (ref "J1") (pin "2") (pinfunction "2_2") (pintype "bidirectional"))
      (node (ref "J1") (pin "8") (pinfunction "8_8") (pintype "bidirectional"))
    )
    (net (code "29") (name "Net-(FB5-Pad2)") (class "Default")
      (node (ref "FB5") (pin "2") (pinfunction "2_2") (pintype "passive"))
      (node (ref "J1") (pin "12") (pinfunction "12_12") (pintype "bidirectional"))
    )
    (net (code "30") (name "Net-(FB6-Pad1)") (class "Default")
      (node (ref "FB6") (pin "1") (pinfunction "1_1") (pintype "passive"))
      (node (ref "J1") (pin "7") (pinfunction "7_7") (pintype "bidirectional"))
    )
    (net (code "31") (name "Net-(IC6-OUT)") (class "Default")
      (node (ref "IC6") (pin "1") (pinfunction "OUT_1") (pintype "output"))
      (node (ref "R43") (pin "2") (pinfunction "2_2") (pintype "passive"))
      (node (ref "R45") (pin "1") (pinfunction "1_1") (pintype "passive"))
    )
    (net (code "32") (name "Net-(IC6-V+)") (class "Default")
      (node (ref "C87") (pin "1") (pinfunction "1_1") (pintype "passive"))
      (node (ref "IC6") (pin "5") (pinfunction "V+_5") (pintype "power_in"))
      (node (ref "R37") (pin "2") (pinfunction "2_2") (pintype "passive"))
      (node (ref "R44") (pin "2") (pinfunction "2_2") (pintype "passive"))
      (node (ref "R7") (pin "2") (pinfunction "2_2") (pintype "passive"))
      (node (ref "R8") (pin "2") (pinfunction "2_2") (pintype "passive"))
      (node (ref "T1") (pin "3") (pinfunction "C_3") (pintype "passive"))
    )
    (net (code "33") (name "Net-(IC6-VIN-)") (class "Default")
      (node (ref "IC6") (pin "3") (pinfunction "VIN-_3") (pintype "input"))
      (node (ref "R44") (pin "1") (pinfunction "1_1") (pintype "passive"))
    )
    (net (code "34") (name "Net-(IC7-OUT)") (class "Default")
      (node (ref "IC7") (pin "1") (pinfunction "OUT_1") (pintype "output"))
      (node (ref "R46") (pin "2") (pinfunction "2_2") (pintype "passive"))
      (node (ref "R53") (pin "1") (pinfunction "1_1") (pintype "passive"))
    )
    (net (code "35") (name "Net-(IC7-VIN-)") (class "Default")
      (node (ref "IC7") (pin "3") (pinfunction "VIN-_3") (pintype "input"))
      (node (ref "R49") (pin "1") (pinfunction "1_1") (pintype "passive"))
    )
    (net (code "36") (name "Net-(IC9-ADCIN)") (class "Default")
      (node (ref "C48") (pin "2") (pinfunction "2_2") (pintype "passive"))
      (node (ref "IC9") (pin "14") (pinfunction "ADCIN_14") (pintype "input"))
      (node (ref "R56") (pin "2") (pinfunction "2_2") (pintype "passive"))
    )
    (net (code "37") (name "Net-(IC9-AVDD)") (class "Default")
      (node (ref "C41") (pin "2") (pinfunction "2_2") (pintype "passive"))
      (node (ref "C42") (pin "1") (pinfunction "1_1") (pintype "passive"))
      (node (ref "IC9") (pin "15") (pinfunction "AVDD_15") (pintype "power_in"))
      (node (ref "R83") (pin "2") (pinfunction "2_2") (pintype "passive"))
    )
    (net (code "38") (name "Net-(IC9-MUXOUT)") (class "Default")
      (node (ref "IC9") (pin "13") (pinfunction "MUXOUT_13") (pintype "output"))
      (node (ref "R56") (pin "1") (pinfunction "1_1") (pintype "passive"))
    )
    (net (code "39") (name "Net-(IC13-ERROR)") (class "Default")
      (node (ref "C90") (pin "1") (pinfunction "1_1") (pintype "passive"))
      (node (ref "IC13") (pin "4") (pinfunction "ERROR_4") (pintype "passive"))
      (node (ref "R122") (pin "1") (pinfunction "1_1") (pintype "passive"))
      (node (ref "R123") (pin "2") (pinfunction "2_2") (pintype "passive"))
    )
    (net (code "40") (name "Net-(IC13-VOUT)") (class "Default")
      (node (ref "C19") (pin "2") (pinfunction "2_2") (pintype "passive"))
      (node (ref "C45") (pin "1") (pinfunction "1_1") (pintype "passive"))
      (node (ref "C90") (pin "2") (pinfunction "2_2") (pintype "passive"))
      (node (ref "IC13") (pin "3") (pinfunction "VOUT_3") (pintype "power_in"))
      (node (ref "IC21") (pin "4") (pinfunction "OUT_4") (pintype "power_in"))
      (node (ref "IC7") (pin "5") (pinfunction "V+_5") (pintype "power_in"))
      (node (ref "R10") (pin "2") (pinfunction "2_2") (pintype "passive"))
      (node (ref "R11") (pin "1") (pinfunction "1_1") (pintype "passive"))
      (node (ref "R122") (pin "2") (pinfunction "2_2") (pintype "passive"))
      (node (ref "R39") (pin "2") (pinfunction "2_2") (pintype "passive"))
      (node (ref "R49") (pin "2") (pinfunction "2_2") (pintype "passive"))
    )
    (net (code "41") (name "Net-(IC15-A0)") (class "Default")
      (node (ref "IC15") (pin "6") (pinfunction "A0_6") (pintype "input"))
      (node (ref "R90") (pin "2") (pinfunction "2_2") (pintype "passive"))
    )
    (net (code "42") (name "Net-(IC15-VOUT)") (class "Default")
      (node (ref "IC15") (pin "1") (pinfunction "VOUT_1") (pintype "output"))
      (node (ref "R117") (pin "2") (pinfunction "2_2") (pintype "passive"))
      (node (ref "R89") (pin "1") (pinfunction "1_1") (pintype "passive"))
    )
    (net (code "43") (name "Net-(IC21-ADJ)") (class "Default")
      (node (ref "IC21") (pin "5") (pinfunction "ADJ_5") (pintype "input"))
      (node (ref "R10") (pin "1") (pinfunction "1_1") (pintype "passive"))
      (node (ref "R13") (pin "2") (pinfunction "2_2") (pintype "passive"))
    )
    (net (code "44") (name "Net-(IC22-IN-)") (class "Default")
      (node (ref "IC22") (pin "4") (pinfunction "IN-_4") (pintype "input"))
      (node (ref "R115") (pin "2") (pinfunction "2_2") (pintype "passive"))
      (node (ref "R116") (pin "1") (pinfunction "1_1") (pintype "passive"))
      (node (ref "R117") (pin "1") (pinfunction "1_1") (pintype "passive"))
    )
    (net (code "45") (name "Net-(IC22-V-)") (class "Default")
      (node (ref "C85") (pin "1") (pinfunction "1_1") (pintype "passive"))
      (node (ref "IC22") (pin "2") (pinfunction "V-_2") (pintype "power_in"))
      (node (ref "IC23") (pin "3") (pinfunction "OUT_3") (pintype "power_in"))
    )
    (net (code "46") (name "Net-(LD1-A)") (class "Default")
      (node (ref "LD1") (pin "2") (pinfunction "A_2") (pintype "passive"))
      (node (ref "R7") (pin "1") (pinfunction "1_1") (pintype "passive"))
    )
    (net (code "47") (name "Net-(LD2-A)") (class "Default")
      (node (ref "LD2") (pin "2") (pinfunction "A_2") (pintype "passive"))
      (node (ref "R11") (pin "2") (pinfunction "2_2") (pintype "passive"))
    )
    (net (code "48") (name "Net-(LD4-A)") (class "Default")
      (node (ref "LD4") (pin "2") (pinfunction "A_2") (pintype "passive"))
      (node (ref "R107") (pin "1") (pinfunction "1_1") (pintype "passive"))
    )
    (net (code "49") (name "Net-(LD12-C)") (class "Default")
      (node (ref "LD12") (pin "1") (pinfunction "C_1") (pintype "passive"))
      (node (ref "R104") (pin "2") (pinfunction "2_2") (pintype "passive"))
    )
    (net (code "50") (name "Net-(T1-B)") (class "Default")
      (node (ref "R12") (pin "1") (pinfunction "1_1") (pintype "passive"))
      (node (ref "R29") (pin "2") (pinfunction "2_2") (pintype "passive"))
      (node (ref "T1") (pin "1") (pinfunction "B_1") (pintype "passive"))
    )
    (net (code "51") (name "Net-(T1-E)") (class "Default")
      (node (ref "R114") (pin "2") (pinfunction "2_2") (pintype "passive"))
      (node (ref "R12") (pin "2") (pinfunction "2_2") (pintype "passive"))
      (node (ref "T1") (pin "2") (pinfunction "E_2") (pintype "passive"))
      (node (ref "U1") (pin "7") (pinfunction "CURRENT_LIMIT(-)_7") (pintype "input"))
    )
    (net (code "52") (name "Net-(T2-D)") (class "Default")
      (node (ref "C67") (pin "1") (pinfunction "1_1") (pintype "passive"))
      (node (ref "J1") (pin "14") (pinfunction "14_14") (pintype "bidirectional"))
      (node (ref "R84") (pin "1") (pinfunction "1_1") (pintype "passive"))
      (node (ref "T2") (pin "3") (pinfunction "D_3") (pintype "passive"))
    )
    (net (code "53") (name "Net-(T2-G)") (class "Default")
      (node (ref "R17") (pin "1") (pinfunction "1_1") (pintype "passive"))
      (node (ref "R40") (pin "1") (pinfunction "1_1") (pintype "passive"))
      (node (ref "T2") (pin "1") (pinfunction "G_1") (pintype "passive"))
      (node (ref "T3") (pin "1") (pinfunction "G_1") (pintype "passive"))
      (node (ref "T6") (pin "3") (pinfunction "D_3") (pintype "passive"))
    )
    (net (code "54") (name "Net-(T3-D)") (class "Default")
      (node (ref "C20") (pin "2") (pinfunction "2_2") (pintype "passive"))
      (node (ref "R35") (pin "1") (pinfunction "1_1") (pintype "passive"))
      (node (ref "T3") (pin "3") (pinfunction "D_3") (pintype "passive"))
      (node (ref "U1") (pin "2") (pinfunction "COMPENSATION/SHUTDOWN_2") (pintype "passive"))
    )
    (net (code "55") (name "Net-(T5-D)") (class "Default")
      (node (ref "C86") (pin "1") (pinfunction "1_1") (pintype "passive"))
      (node (ref "R116") (pin "2") (pinfunction "2_2") (pintype "passive"))
      (node (ref "T5") (pin "3") (pinfunction "D_3") (pintype "passive"))
    )
    (net (code "56") (name "Net-(U1-DRIVER_SINK)") (class "Default")
      (node (ref "R29") (pin "1") (pinfunction "1_1") (pintype "passive"))
      (node (ref "U1") (pin "6") (pinfunction "DRIVER_SINK_6") (pintype "passive"))
    )
    (net (code "57") (name "Net-(U1-VOUT_SENSE)") (class "Default")
      (node (ref "R8") (pin "1") (pinfunction "1_1") (pintype "passive"))
      (node (ref "R9") (pin "2") (pinfunction "2_2") (pintype "passive"))
      (node (ref "U1") (pin "5") (pinfunction "VOUT_SENSE_5") (pintype "input"))
    )
    (net (code "58") (name "P3V3") (class "Default")
      (node (ref "C47") (pin "2") (pinfunction "2_2") (pintype "passive"))
      (node (ref "IC14") (pin "1") (pinfunction "VCC_1") (pintype "power_in"))
      (node (ref "IC9") (pin "16") (pinfunction "DVDD_16") (pintype "power_in"))
      (node (ref "IC9") (pin "5") (pinfunction "A0_5") (pintype "input"))
      (node (ref "R107") (pin "2") (pinfunction "2_2") (pintype "passive"))
      (node (ref "R32") (pin "1") (pinfunction "1_1") (pintype "passive"))
      (node (ref "R51") (pin "1") (pinfunction "1_1") (pintype "passive"))
      (node (ref "R52") (pin "1") (pinfunction "1_1") (pintype "passive"))
      (node (ref "R57") (pin "2") (pinfunction "2_2") (pintype "passive"))
      (node (ref "R83") (pin "1") (pinfunction "1_1") (pintype "passive"))
    )
    (net (code "59") (name "P5V0") (class "Default")
      (node (ref "F1") (pin "1") (pinfunction "1_1") (pintype "passive"))
    )
    (net (code "60") (name "P6V5") (class "Default")
      (node (ref "C78") (pin "1") (pinfunction "1_1") (pintype "passive"))
      (node (ref "C89") (pin "1") (pinfunction "1_1") (pintype "passive"))
      (node (ref "IC13") (pin "2") (pinfunction "VIN_2") (pintype "input"))
      (node (ref "IC21") (pin "2") (pinfunction "IN_2") (pintype "input"))
    )
    (net (code "61") (name "P30V0") (class "Default")
      (node (ref "C32") (pin "2") (pinfunction "2_2") (pintype "passive"))
      (node (ref "R114") (pin "1") (pinfunction "1_1") (pintype "passive"))
      (node (ref "R17") (pin "2") (pinfunction "2_2") (pintype "passive"))
      (node (ref "U1") (pin "1") (pinfunction "+VIN_1") (pintype "power_in"))
    )
    (net (code "62") (name "REF_P3V3") (class "Default")
      (node (ref "C60") (pin "2") (pinfunction "2_2") (pintype "passive"))
      (node (ref "IC15") (pin "3") (pinfunction "VDD_3") (pintype "power_in"))
      (node (ref "R89") (pin "2") (pinfunction "2_2") (pintype "passive"))
      (node (ref "T5") (pin "2") (pinfunction "S_2") (pintype "passive"))
    )
    (net (code "63") (name "unconnected-(IC9-PWRCON-Pad7)") (class "Default")
      (node (ref "IC9") (pin "7") (pinfunction "PWRCON_7") (pintype "output"))
    )
    (net (code "64") (name "unconnected-(U1-SENSE_RESISTOR_OUT-Pad8)") (class "Default")
      (node (ref "U1") (pin "8") (pinfunction "SENSE_RESISTOR_OUT_8") (pintype "passive"))
    )
  )
)
